# 4.net
KiCad netlist of a schematic drawn in Altium Designer
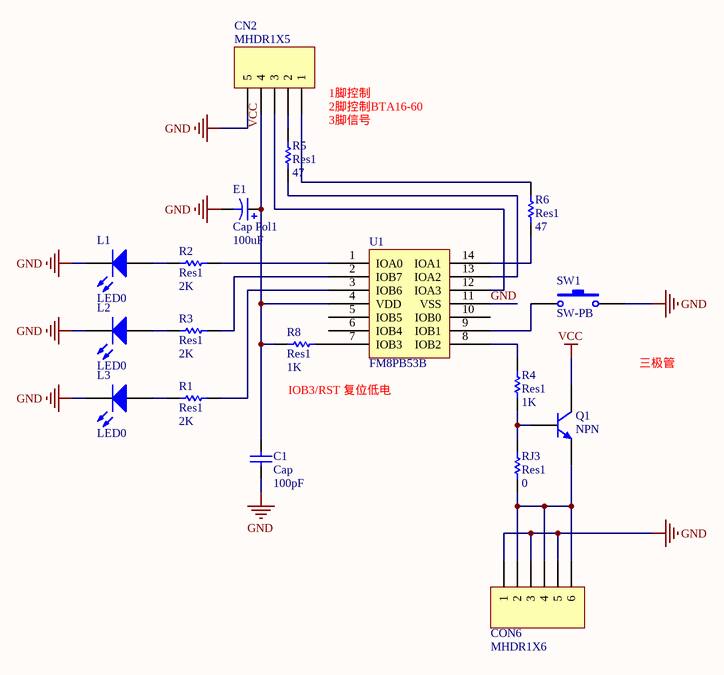
[diagram p0: 4.SchDoc]

(export (version "E")
  (design (tool "Eeschema 10.0.6"))
  (components
    (comp (ref "C1")
      (value "Cap")
      (footprint "C0805")
      (description "Capacitor")
      (fields (field (name "ALTIUM_VALUE") "100pF") (field (name "PUBLISHER") "Altium Limited"))
      (libsource (lib "Miscellaneous Devices") (part "Cap"))
    )
    (comp (ref "CN2")
      (value "MHDR1X5")
      (footprint "HDR1X5")
      (description "Header, 5-Pin")
      (fields (field (name "PUBLISHER") "Altium Limited"))
      (libsource (lib "Miscellaneous Connectors") (part "MHDR1X5"))
    )
    (comp (ref "CON6")
      (value "MHDR1X6")
      (footprint "HDR1X6")
      (description "Header, 6-Pin")
      (fields (field (name "PUBLISHER") "Altium Limited"))
      (libsource (lib "Miscellaneous Connectors") (part "MHDR1X6"))
    )
    (comp (ref "E1")
      (value "Cap Pol1")
      (footprint "CAP")
      (description "Polarized Capacitor (Radial)")
      (fields (field (name "ALTIUM_VALUE") "100uF") (field (name "PUBLISHER") "Altium Limited"))
      (libsource (lib "Miscellaneous Devices") (part "Cap Pol1"))
    )
    (comp (ref "L1")
      (value "LED0")
      (footprint "LED_DIP")
      (description "Typical INFRARED GaAs LED")
      (fields (field (name "PUBLISHER") "Altium Limited"))
      (libsource (lib "Miscellaneous Devices") (part "LED0"))
    )
    (comp (ref "L2")
      (value "LED0")
      (footprint "LED_DIP")
      (description "Typical INFRARED GaAs LED")
      (fields (field (name "PUBLISHER") "Altium Limited"))
      (libsource (lib "Miscellaneous Devices") (part "LED0"))
    )
    (comp (ref "L3")
      (value "LED0")
      (footprint "LED_DIP")
      (description "Typical INFRARED GaAs LED")
      (fields (field (name "PUBLISHER") "Altium Limited"))
      (libsource (lib "Miscellaneous Devices") (part "LED0"))
    )
    (comp (ref "Q1")
      (value "NPN")
      (footprint "SOT23_N")
      (description "NPN Bipolar Transistor")
      (fields (field (name "PUBLISHER") "Altium Limited"))
      (libsource (lib "Miscellaneous Devices") (part "NPN"))
    )
    (comp (ref "R1")
      (value "Res1")
      (footprint "6-0805_N")
      (description "Resistor")
      (fields (field (name "ALTIUM_VALUE") "2K") (field (name "PUBLISHER") "Altium Limited"))
      (libsource (lib "Miscellaneous Devices") (part "Res1"))
    )
    (comp (ref "R2")
      (value "Res1")
      (footprint "6-0805_N")
      (description "Resistor")
      (fields (field (name "ALTIUM_VALUE") "2K") (field (name "PUBLISHER") "Altium Limited"))
      (libsource (lib "Miscellaneous Devices") (part "Res1"))
    )
    (comp (ref "R3")
      (value "Res1")
      (footprint "6-0805_N")
      (description "Resistor")
      (fields (field (name "ALTIUM_VALUE") "2K") (field (name "PUBLISHER") "Altium Limited"))
      (libsource (lib "Miscellaneous Devices") (part "Res1"))
    )
    (comp (ref "R4")
      (value "Res1")
      (footprint "6-0805_N")
      (description "Resistor")
      (fields (field (name "ALTIUM_VALUE") "1K") (field (name "PUBLISHER") "Altium Limited"))
      (libsource (lib "Miscellaneous Devices") (part "Res1"))
    )
    (comp (ref "R5")
      (value "Res1")
      (footprint "6-0805_N")
      (description "Resistor")
      (fields (field (name "ALTIUM_VALUE") "47") (field (name "PUBLISHER") "Altium Limited"))
      (libsource (lib "Miscellaneous Devices") (part "Res1"))
    )
    (comp (ref "R6")
      (value "Res1")
      (footprint "6-0805_N")
      (description "Resistor")
      (fields (field (name "ALTIUM_VALUE") "47") (field (name "PUBLISHER") "Altium Limited"))
      (libsource (lib "Miscellaneous Devices") (part "Res1"))
    )
    (comp (ref "R8")
      (value "Res1")
      (footprint "6-0805_N")
      (description "Resistor")
      (fields (field (name "ALTIUM_VALUE") "1K") (field (name "PUBLISHER") "Altium Limited"))
      (libsource (lib "Miscellaneous Devices") (part "Res1"))
    )
    (comp (ref "RJ3")
      (value "Res1")
      (footprint "6-0805_N")
      (description "Resistor")
      (fields (field (name "ALTIUM_VALUE") "0") (field (name "PUBLISHER") "Altium Limited"))
      (libsource (lib "Miscellaneous Devices") (part "Res1"))
    )
    (comp (ref "SW1")
      (value "SW-PB")
      (footprint "SW_DIP")
      (description "Switch")
      (fields (field (name "PUBLISHER") "Altium Limited"))
      (libsource (lib "Miscellaneous Devices") (part "SW-PB"))
    )
    (comp (ref "U1") (value "FM8PB53B") (footprint "SOP14") (libsource (lib "4") (part "FM8PB53B")))
  )
  (nets
    (net (code "1") (name "GND") (class "Default")
      (node (ref "C1") (pin "2") (pinfunction "2_2") (pintype "passive"))
      (node (ref "CN2") (pin "5") (pinfunction "5_5") (pintype "passive"))
      (node (ref "CON6") (pin "1") (pinfunction "1_1") (pintype "passive"))
      (node (ref "CON6") (pin "3") (pinfunction "3_3") (pintype "passive"))
      (node (ref "CON6") (pin "5") (pinfunction "5_5") (pintype "passive"))
      (node (ref "E1") (pin "2") (pinfunction "2_2") (pintype "passive"))
      (node (ref "L1") (pin "2") (pinfunction "K_2") (pintype "passive"))
      (node (ref "L2") (pin "2") (pinfunction "K_2") (pintype "passive"))
      (node (ref "L3") (pin "2") (pinfunction "K_2") (pintype "passive"))
      (node (ref "SW1") (pin "2") (pinfunction "2_2") (pintype "passive"))
      (node (ref "U1") (pin "11") (pinfunction "VSS_11") (pintype "passive"))
    )
    (net (code "2") (name "Net-(CN2-Pad1)") (class "Default")
      (node (ref "CN2") (pin "1") (pinfunction "1_1") (pintype "passive"))
      (node (ref "R6") (pin "1") (pinfunction "1_1") (pintype "passive"))
    )
    (net (code "3") (name "Net-(CN2-Pad2)") (class "Default")
      (node (ref "CN2") (pin "2") (pinfunction "2_2") (pintype "passive"))
      (node (ref "R5") (pin "2") (pinfunction "2_2") (pintype "passive"))
    )
    (net (code "4") (name "Net-(L1-A)") (class "Default")
      (node (ref "L1") (pin "1") (pinfunction "A_1") (pintype "passive"))
      (node (ref "R2") (pin "1") (pinfunction "1_1") (pintype "passive"))
    )
    (net (code "5") (name "Net-(L2-A)") (class "Default")
      (node (ref "L2") (pin "1") (pinfunction "A_1") (pintype "passive"))
      (node (ref "R3") (pin "1") (pinfunction "1_1") (pintype "passive"))
    )
    (net (code "6") (name "Net-(L3-A)") (class "Default")
      (node (ref "L3") (pin "1") (pinfunction "A_1") (pintype "passive"))
      (node (ref "R1") (pin "1") (pinfunction "1_1") (pintype "passive"))
    )
    (net (code "7") (name "Net-(Q1-B)") (class "Default")
      (node (ref "Q1") (pin "2") (pinfunction "B_2") (pintype "passive"))
      (node (ref "R4") (pin "1") (pinfunction "1_1") (pintype "passive"))
      (node (ref "RJ3") (pin "2") (pinfunction "2_2") (pintype "passive"))
    )
    (net (code "8") (name "Net-(Q1-E)") (class "Default")
      (node (ref "CON6") (pin "2") (pinfunction "2_2") (pintype "passive"))
      (node (ref "CON6") (pin "4") (pinfunction "4_4") (pintype "passive"))
      (node (ref "CON6") (pin "6") (pinfunction "6_6") (pintype "passive"))
      (node (ref "Q1") (pin "3") (pinfunction "E_3") (pintype "passive"))
      (node (ref "RJ3") (pin "1") (pinfunction "1_1") (pintype "passive"))
    )
    (net (code "9") (name "Net-(U1-IOA0)") (class "Default")
      (node (ref "R2") (pin "2") (pinfunction "2_2") (pintype "passive"))
      (node (ref "U1") (pin "1") (pinfunction "IOA0_1") (pintype "passive"))
    )
    (net (code "10") (name "Net-(U1-IOA1)") (class "Default")
      (node (ref "R6") (pin "2") (pinfunction "2_2") (pintype "passive"))
      (node (ref "U1") (pin "14") (pinfunction "IOA1_14") (pintype "passive"))
    )
    (net (code "11") (name "Net-(U1-IOA2)") (class "Default")
      (node (ref "R5") (pin "1") (pinfunction "1_1") (pintype "passive"))
      (node (ref "U1") (pin "13") (pinfunction "IOA2_13") (pintype "passive"))
    )
    (net (code "12") (name "Net-(U1-IOA3)") (class "Default")
      (node (ref "CN2") (pin "3") (pinfunction "3_3") (pintype "passive"))
      (node (ref "U1") (pin "12") (pinfunction "IOA3_12") (pintype "passive"))
    )
    (net (code "13") (name "Net-(U1-IOB1)") (class "Default")
      (node (ref "SW1") (pin "1") (pinfunction "1_1") (pintype "passive"))
      (node (ref "U1") (pin "9") (pinfunction "IOB1_9") (pintype "passive"))
    )
    (net (code "14") (name "Net-(U1-IOB2)") (class "Default")
      (node (ref "R4") (pin "2") (pinfunction "2_2") (pintype "passive"))
      (node (ref "U1") (pin "8") (pinfunction "IOB2_8") (pintype "passive"))
    )
    (net (code "15") (name "Net-(U1-IOB3)") (class "Default")
      (node (ref "R8") (pin "2") (pinfunction "2_2") (pintype "passive"))
      (node (ref "U1") (pin "7") (pinfunction "IOB3_7") (pintype "passive"))
    )
    (net (code "16") (name "Net-(U1-IOB6)") (class "Default")
      (node (ref "R1") (pin "2") (pinfunction "2_2") (pintype "passive"))
      (node (ref "U1") (pin "3") (pinfunction "IOB6_3") (pintype "passive"))
    )
    (net (code "17") (name "Net-(U1-IOB7)") (class "Default")
      (node (ref "R3") (pin "2") (pinfunction "2_2") (pintype "passive"))
      (node (ref "U1") (pin "2") (pinfunction "IOB7_2") (pintype "passive"))
    )
    (net (code "18") (name "VCC") (class "Default")
      (node (ref "C1") (pin "1") (pinfunction "1_1") (pintype "passive"))
      (node (ref "CN2") (pin "4") (pinfunction "4_4") (pintype "passive"))
      (node (ref "E1") (pin "1") (pinfunction "1_1") (pintype "passive"))
      (node (ref "Q1") (pin "1") (pinfunction "C_1") (pintype "passive"))
      (node (ref "R8") (pin "1") (pinfunction "1_1") (pintype "passive"))
      (node (ref "U1") (pin "4") (pinfunction "VDD_4") (pintype "passive"))
    )
    (net (code "19") (name "unconnected-(U1-IOB0-Pad10)") (class "Default")
      (node (ref "U1") (pin "10") (pinfunction "IOB0_10") (pintype "passive"))
    )
    (net (code "20") (name "unconnected-(U1-IOB4-Pad6)") (class "Default")
      (node (ref "U1") (pin "6") (pinfunction "IOB4_6") (pintype "passive"))
    )
    (net (code "21") (name "unconnected-(U1-IOB5-Pad5)") (class "Default")
      (node (ref "U1") (pin "5") (pinfunction "IOB5_5") (pintype "passive"))
    )
  )
)
